# mi-led.net
KiCad netlist of a schematic drawn in EAGLE
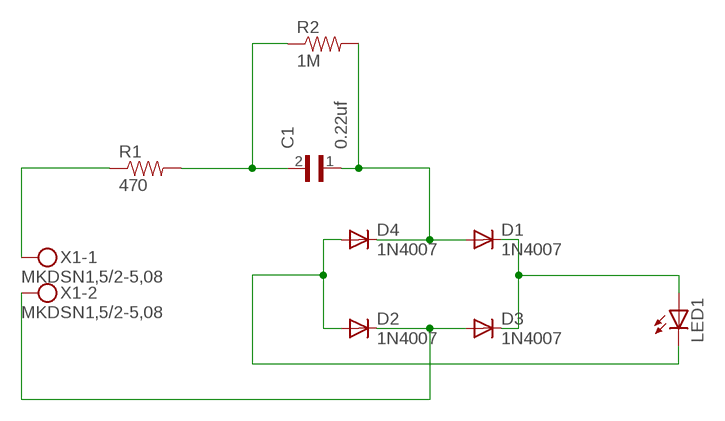
[diagram p0: schematic, sheet 1]

(export (version "E")
  (design (tool "Eeschema 10.0.6"))
  (components
    (comp (ref "C1")
      (value "0.22uf")
      (footprint "eagle-import:WCAP-FTX2_12.5X15X14X8.5")
      (libsource (lib "eagle-import") (part "WCAP-FTX2_890324024003CS"))
    )
    (comp (ref "D1")
      (value "1N4007")
      (footprint "eagle-import:DO41-10")
      (libsource (lib "eagle-import") (part "1N4004"))
    )
    (comp (ref "D2")
      (value "1N4007")
      (footprint "eagle-import:DO41-10")
      (libsource (lib "eagle-import") (part "1N4004"))
    )
    (comp (ref "D3")
      (value "1N4007")
      (footprint "eagle-import:DO41-10")
      (libsource (lib "eagle-import") (part "1N4004"))
    )
    (comp (ref "D4")
      (value "1N4007")
      (footprint "eagle-import:DO41-10")
      (libsource (lib "eagle-import") (part "1N4004"))
    )
    (comp (ref "LED1")
      (value "LED5MM")
      (footprint "eagle-import:LED5MM")
      (libsource (lib "eagle-import") (part "LED5MM"))
    )
    (comp (ref "R1")
      (value "470")
      (footprint "eagle-import:AXIAL-0.5")
      (libsource (lib "eagle-import") (part "RESISTORPTH-1/2W"))
    )
    (comp (ref "R2")
      (value "1M")
      (footprint "eagle-import:AXIAL-0.5")
      (libsource (lib "eagle-import") (part "RESISTORPTH-1/2W"))
    )
    (comp (ref "X1")
      (value "MKDSN1,5/2-5,08")
      (footprint "eagle-import:MKDSN1,5_2-5,08")
      (libsource (lib "eagle-import") (part "MKDSN1,5/2-5,08"))
    )
  )
  (nets
    (net (code "1") (name "Net-(D1-PadC)") (class "Default")
      (node (ref "D1") (pin "C") (pinfunction "C_C") (pintype "passive"))
      (node (ref "D3") (pin "C") (pinfunction "C_C") (pintype "passive"))
      (node (ref "LED1") (pin "A") (pinfunction "A_A") (pintype "passive"))
    )
    (net (code "2") (name "Net-(LED1-C)") (class "Default")
      (node (ref "D2") (pin "A") (pinfunction "A_A") (pintype "passive"))
      (node (ref "D4") (pin "A") (pinfunction "A_A") (pintype "passive"))
      (node (ref "LED1") (pin "K") (pinfunction "C_K") (pintype "passive"))
    )
    (net (code "3") (name "Net-(R1-1)") (class "Default")
      (node (ref "R1") (pin "P$1") (pinfunction "1_P$1") (pintype "passive"))
      (node (ref "X1") (pin "1") (pinfunction "KL_1") (pintype "passive"))
    )
    (net (code "4") (name "Net-(R1-2)") (class "Default")
      (node (ref "C1") (pin "2") (pinfunction "2_2") (pintype "passive"))
      (node (ref "R1") (pin "P$2") (pinfunction "2_P$2") (pintype "passive"))
      (node (ref "R2") (pin "P$1") (pinfunction "1_P$1") (pintype "passive"))
    )
    (net (code "5") (name "Net-(R2-2)") (class "Default")
      (node (ref "C1") (pin "1") (pinfunction "1_1") (pintype "passive"))
      (node (ref "D1") (pin "A") (pinfunction "A_A") (pintype "passive"))
      (node (ref "D4") (pin "C") (pinfunction "C_C") (pintype "passive"))
      (node (ref "R2") (pin "P$2") (pinfunction "2_P$2") (pintype "passive"))
    )
    (net (code "6") (name "Net-(X1B-KL)") (class "Default")
      (node (ref "D2") (pin "C") (pinfunction "C_C") (pintype "passive"))
      (node (ref "D3") (pin "A") (pinfunction "A_A") (pintype "passive"))
      (node (ref "X1") (pin "2") (pinfunction "KL_2") (pintype "passive"))
    )
  )
)
